# POWER.net
KiCad netlist of a schematic drawn in Altium Designer
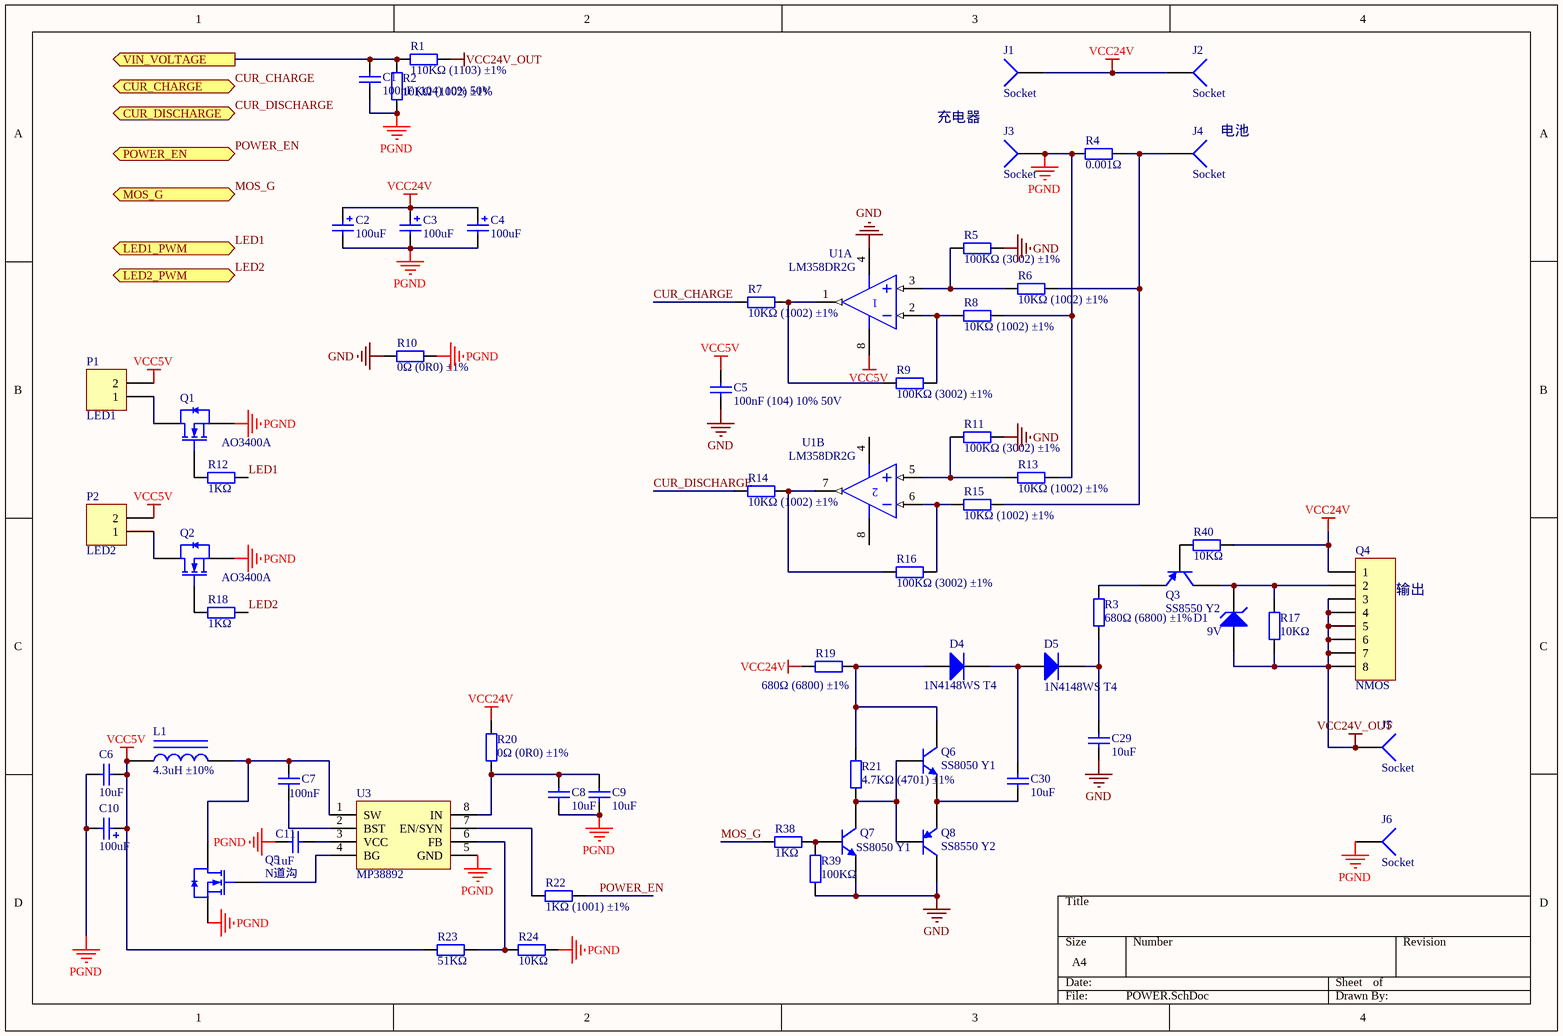
[diagram p0: POWER.SchDoc]

(export (version "E")
  (design (tool "Eeschema 10.0.6"))
  (components
    (comp (ref "C1")
      (value "100nF (104) 10% 50V")
      (footprint "0603_C")
      (description "贴片电容")
      (libsource (lib "Miscellaneous Devices LC") (part "0603 100nF (104) 10% 50V"))
    )
    (comp (ref "C2")
      (value "100uF")
      (footprint "CC6.56.5")
      (description "钽电容")
      (libsource (lib "Miscellaneous Devices LC") (part "3528 100uF (107) 10% 6.3V"))
    )
    (comp (ref "C3")
      (value "100uF")
      (footprint "CC6.56.5")
      (description "钽电容")
      (libsource (lib "Miscellaneous Devices LC") (part "3528 100uF (107) 10% 6.3V"))
    )
    (comp (ref "C4")
      (value "100uF")
      (footprint "CC6.56.5")
      (description "钽电容")
      (libsource (lib "Miscellaneous Devices LC") (part "3528 100uF (107) 10% 6.3V"))
    )
    (comp (ref "C5")
      (value "100nF (104) 10% 50V")
      (footprint "0603_C")
      (description "贴片电容")
      (libsource (lib "Miscellaneous Devices LC") (part "0603 100nF (104) 10% 50V"))
    )
    (comp (ref "C6")
      (value "10uF")
      (footprint "0805_C")
      (description "贴片电容")
      (libsource (lib "Miscellaneous Devices LC") (part "0805 10uF (106) 10% 25V"))
    )
    (comp (ref "C7")
      (value "100nF")
      (footprint "0603_C")
      (description "贴片电容")
      (libsource (lib "Miscellaneous Devices LC") (part "0603 100nF (104) 10% 50V"))
    )
    (comp (ref "C8")
      (value "10uF")
      (footprint "0805_C")
      (description "贴片电容")
      (libsource (lib "Miscellaneous Devices LC") (part "0805 10uF (106) 10% 25V"))
    )
    (comp (ref "C9")
      (value "10uF")
      (footprint "0805_C")
      (description "贴片电容")
      (libsource (lib "Miscellaneous Devices LC") (part "0805 10uF (106) 10% 25V"))
    )
    (comp (ref "C10")
      (value "100uF")
      (footprint "CC6.56.5")
      (description "钽电容")
      (libsource (lib "Miscellaneous Devices LC") (part "3528 100uF (107) 10% 6.3V"))
    )
    (comp (ref "C11")
      (value "1uF")
      (footprint "0603_C")
      (description "贴片电容")
      (libsource (lib "Miscellaneous Devices LC") (part "0603 1uF (105) 10% 50V"))
    )
    (comp (ref "C29")
      (value "10uF")
      (footprint "0805_C")
      (description "贴片电容")
      (libsource (lib "Miscellaneous Devices LC") (part "0805 10uF (106) 10% 25V"))
    )
    (comp (ref "C30")
      (value "10uF")
      (footprint "0805_C")
      (description "贴片电容")
      (libsource (lib "Miscellaneous Devices LC") (part "0805 10uF (106) 10% 25V"))
    )
    (comp (ref "D1")
      (value "9V")
      (footprint "LL-34")
      (description "稳压二极管")
      (libsource (lib "Miscellaneous Devices LC") (part "LL-34 ZMM5V6"))
    )
    (comp (ref "D4")
      (value "1N4148WS T4")
      (footprint "SOD-323")
      (description "二极管")
      (libsource (lib "Miscellaneous Devices LC") (part "SOD-323 1N4148WS T4"))
    )
    (comp (ref "D5")
      (value "1N4148WS T4")
      (footprint "SOD-323")
      (description "二极管")
      (libsource (lib "Miscellaneous Devices LC") (part "SOD-323 1N4148WS T4"))
    )
    (comp (ref "J1")
      (value "Socket")
      (footprint "PIN1")
      (fields (field (name "PUBLISHER") "Altium Limited"))
      (libsource (lib "Miscellaneous Connectors") (part "Socket"))
    )
    (comp (ref "J2")
      (value "Socket")
      (footprint "PIN1")
      (fields (field (name "PUBLISHER") "Altium Limited"))
      (libsource (lib "Miscellaneous Connectors") (part "Socket"))
    )
    (comp (ref "J3")
      (value "Socket")
      (footprint "PIN1")
      (fields (field (name "PUBLISHER") "Altium Limited"))
      (libsource (lib "Miscellaneous Connectors") (part "Socket"))
    )
    (comp (ref "J4")
      (value "Socket")
      (footprint "PIN1")
      (fields (field (name "PUBLISHER") "Altium Limited"))
      (libsource (lib "Miscellaneous Connectors") (part "Socket"))
    )
    (comp (ref "J5")
      (value "Socket")
      (footprint "PIN1")
      (fields (field (name "PUBLISHER") "Altium Limited"))
      (libsource (lib "Miscellaneous Connectors") (part "Socket"))
    )
    (comp (ref "J6")
      (value "Socket")
      (footprint "PIN1")
      (fields (field (name "PUBLISHER") "Altium Limited"))
      (libsource (lib "Miscellaneous Connectors") (part "Socket"))
    )
    (comp (ref "L1")
      (value "4.3uH ±10%")
      (footprint "2225")
      (description "贴片电感")
      (libsource (lib "Miscellaneous Devices LC") (part "0805 10uH 10%"))
    )
    (comp (ref "P1")
      (value "LED1")
      (footprint "HDR1X2")
      (description "Header, 2-Pin")
      (fields (field (name "PUBLISHER") "Altium Limited"))
      (libsource (lib "Miscellaneous Connectors") (part "Header 2"))
    )
    (comp (ref "P2")
      (value "LED2")
      (footprint "HDR1X2")
      (description "Header, 2-Pin")
      (fields (field (name "PUBLISHER") "Altium Limited"))
      (libsource (lib "Miscellaneous Connectors") (part "Header 2"))
    )
    (comp (ref "Q1")
      (value "AO3400A")
      (footprint "SOT-23-3L")
      (description "MOS(场效应管)")
      (libsource (lib "Miscellaneous Devices LC") (part "AO3400A N道沟 X0YV1T SOT-23"))
    )
    (comp (ref "Q2")
      (value "AO3400A")
      (footprint "SOT-23-3L")
      (description "MOS(场效应管)")
      (libsource (lib "Miscellaneous Devices LC") (part "AO3400A N道沟 X0YV1T SOT-23"))
    )
    (comp (ref "Q3")
      (value "SS8550 Y2")
      (footprint "SOT-23(SOT-23-3)")
      (description "三极管")
      (libsource (lib "Miscellaneous Devices LC") (part "SOT-23 SS8550 Y2"))
    )
    (comp (ref "Q4")
      (value "NMOS")
      (footprint "TO-263-7")
      (description "Header, 8-Pin")
      (fields (field (name "PUBLISHER") "Altium Limited"))
      (libsource (lib "Miscellaneous Connectors") (part "Header 8"))
    )
    (comp (ref "Q5")
      (value "N道沟")
      (footprint "TO-252-2")
      (description "MOS(场效应管)")
      (libsource (lib "Miscellaneous Devices LC") (part "AO3400A N道沟 X0YV1T SOT-23"))
    )
    (comp (ref "Q6")
      (value "SS8050 Y1")
      (footprint "SOT-23(SOT-23-3)")
      (description "三极管")
      (libsource (lib "Miscellaneous Devices LC") (part "SOT-23 SS8050 Y1"))
    )
    (comp (ref "Q7")
      (value "SS8050 Y1")
      (footprint "SOT-23(SOT-23-3)")
      (description "三极管")
      (libsource (lib "Miscellaneous Devices LC") (part "SOT-23 SS8050 Y1"))
    )
    (comp (ref "Q8")
      (value "SS8550 Y2")
      (footprint "SOT-23(SOT-23-3)")
      (description "三极管")
      (libsource (lib "Miscellaneous Devices LC") (part "SOT-23 SS8550 Y2"))
    )
    (comp (ref "R1")
      (value "110KΩ (1103) ±1%")
      (footprint "0603_R")
      (description "贴片电阻")
      (libsource (lib "Miscellaneous Devices LC") (part "0603 110KΩ (1103) 1%"))
    )
    (comp (ref "R2")
      (value "10KΩ (1002) ±1%")
      (footprint "0603_R")
      (description "贴片电阻")
      (libsource (lib "") (part "0603 10KΩ (1002) 1%_1"))
    )
    (comp (ref "R3")
      (value "680Ω (6800) ±1%")
      (footprint "0603_R")
      (description "贴片电阻")
      (libsource (lib "") (part "0603 680Ω (6800) 1%_1"))
    )
    (comp (ref "R4")
      (value "0.001Ω")
      (footprint "2512_R")
      (description "贴片电阻")
      (libsource (lib "") (part "0603 0Ω (0R0) 1%_1"))
    )
    (comp (ref "R5")
      (value "100KΩ (3002) ±1%")
      (footprint "0603_R")
      (description "贴片电阻")
      (libsource (lib "") (part "0603 30KΩ (3002) 1%_2"))
    )
    (comp (ref "R6")
      (value "10KΩ (1002) ±1%")
      (footprint "0603_R")
      (description "贴片电阻")
      (libsource (lib "Miscellaneous Devices LC") (part "0603 10KΩ (1002) 1%"))
    )
    (comp (ref "R7")
      (value "10KΩ (1002) ±1%")
      (footprint "0603_R")
      (description "贴片电阻")
      (libsource (lib "Miscellaneous Devices LC") (part "0603 10KΩ (1002) 1%"))
    )
    (comp (ref "R8")
      (value "10KΩ (1002) ±1%")
      (footprint "0603_R")
      (description "贴片电阻")
      (libsource (lib "Miscellaneous Devices LC") (part "0603 10KΩ (1002) 1%"))
    )
    (comp (ref "R9")
      (value "100KΩ (3002) ±1%")
      (footprint "0603_R")
      (description "贴片电阻")
      (libsource (lib "Miscellaneous Devices LC") (part "0603 30KΩ (3002) 1%"))
    )
    (comp (ref "R10")
      (value "0Ω (0R0) ±1%")
      (footprint "0603_R")
      (description "贴片电阻")
      (libsource (lib "") (part "0603 0Ω (0R0) 1%_2"))
    )
    (comp (ref "R11")
      (value "100KΩ (3002) ±1%")
      (footprint "0603_R")
      (description "贴片电阻")
      (libsource (lib "") (part "0603 30KΩ (3002) 1%_2"))
    )
    (comp (ref "R12")
      (value "1KΩ")
      (footprint "0603_R")
      (description "贴片电阻")
      (libsource (lib "Miscellaneous Devices LC") (part "0603 1KΩ (1001) 1%"))
    )
    (comp (ref "R13")
      (value "10KΩ (1002) ±1%")
      (footprint "0603_R")
      (description "贴片电阻")
      (libsource (lib "Miscellaneous Devices LC") (part "0603 10KΩ (1002) 1%"))
    )
    (comp (ref "R14")
      (value "10KΩ (1002) ±1%")
      (footprint "0603_R")
      (description "贴片电阻")
      (libsource (lib "Miscellaneous Devices LC") (part "0603 10KΩ (1002) 1%"))
    )
    (comp (ref "R15")
      (value "10KΩ (1002) ±1%")
      (footprint "0603_R")
      (description "贴片电阻")
      (libsource (lib "Miscellaneous Devices LC") (part "0603 10KΩ (1002) 1%"))
    )
    (comp (ref "R16")
      (value "100KΩ (3002) ±1%")
      (footprint "0603_R")
      (description "贴片电阻")
      (libsource (lib "Miscellaneous Devices LC") (part "0603 30KΩ (3002) 1%"))
    )
    (comp (ref "R17")
      (value "10KΩ")
      (footprint "0603_R")
      (description "贴片电阻")
      (libsource (lib "") (part "0603 10KΩ (1002) 1%_1"))
    )
    (comp (ref "R18")
      (value "1KΩ")
      (footprint "0603_R")
      (description "贴片电阻")
      (libsource (lib "Miscellaneous Devices LC") (part "0603 1KΩ (1001) 1%"))
    )
    (comp (ref "R19")
      (value "680Ω (6800) ±1%")
      (footprint "0603_R")
      (description "贴片电阻")
      (libsource (lib "Miscellaneous Devices LC") (part "0603 680Ω (6800) 1%"))
    )
    (comp (ref "R20")
      (value "0Ω (0R0) ±1%")
      (footprint "0603_R")
      (description "贴片电阻")
      (libsource (lib "Miscellaneous Devices LC") (part "0603 0Ω (0R0) 1%"))
    )
    (comp (ref "R21")
      (value "4.7KΩ (4701) ±1%")
      (footprint "0603_R")
      (description "贴片电阻")
      (libsource (lib "Miscellaneous Devices LC") (part "0603 4.7KΩ (4701) 1%"))
    )
    (comp (ref "R22")
      (value "1KΩ (1001) ±1%")
      (footprint "0603_R")
      (description "贴片电阻")
      (libsource (lib "") (part "0603 1KΩ (1001) 1%_1"))
    )
    (comp (ref "R23")
      (value "51KΩ")
      (footprint "0603_R")
      (description "贴片电阻")
      (libsource (lib "Miscellaneous Devices LC") (part "0603 51KΩ (5102) 1%"))
    )
    (comp (ref "R24")
      (value "10KΩ")
      (footprint "0603_R")
      (description "贴片电阻")
      (libsource (lib "") (part "0603 10KΩ (1002) 1%_2"))
    )
    (comp (ref "R38")
      (value "1KΩ")
      (footprint "0603_R")
      (description "贴片电阻")
      (libsource (lib "") (part "0603 1KΩ (1001) 1%_1"))
    )
    (comp (ref "R39")
      (value "100KΩ")
      (footprint "0603_R")
      (description "贴片电阻")
      (libsource (lib "") (part "0603 30KΩ (3002) 1%_1"))
    )
    (comp (ref "R40")
      (value "10KΩ")
      (footprint "0603_R")
      (description "贴片电阻")
      (libsource (lib "") (part "0603 10KΩ (1002) 1%_2"))
    )
    (comp (ref "U1")
      (value "LM358DR2G")
      (footprint "SOIC-8_150mil")
      (description "通用运放")
      (libsource (lib "Miscellaneous Devices LC") (part "LM358DR2G"))
    )
    (comp (ref "U3")
      (value "MP38892")
      (footprint "SOIC-8_EP_150mil")
      (libsource (lib "MySchlib") (part "MP38892"))
    )
  )
  (nets
    (net (code "1") (name "/CUR_CHARGE") (class "Default")
      (node (ref "R7") (pin "1") (pinfunction "1_1") (pintype "passive"))
    )
    (net (code "2") (name "/CUR_DISCHARGE") (class "Default")
      (node (ref "R14") (pin "1") (pinfunction "1_1") (pintype "passive"))
    )
    (net (code "3") (name "/LED1") (class "Default")
      (node (ref "R12") (pin "1") (pinfunction "1_1") (pintype "passive"))
    )
    (net (code "4") (name "/LED2") (class "Default")
      (node (ref "R18") (pin "1") (pinfunction "1_1") (pintype "passive"))
    )
    (net (code "5") (name "/MOS_G") (class "Default")
      (node (ref "R38") (pin "1") (pinfunction "1_1") (pintype "passive"))
    )
    (net (code "6") (name "/POWER_EN") (class "Default")
      (node (ref "R22") (pin "2") (pinfunction "2_2") (pintype "passive"))
    )
    (net (code "7") (name "/VIN_VOLTAGE") (class "Default")
      (node (ref "C1") (pin "1") (pinfunction "1_1") (pintype "passive"))
      (node (ref "R1") (pin "2") (pinfunction "2_2") (pintype "passive"))
      (node (ref "R2") (pin "2") (pinfunction "2_2") (pintype "passive"))
    )
    (net (code "8") (name "GND") (class "Default")
      (node (ref "C29") (pin "1") (pinfunction "1_1") (pintype "passive"))
      (node (ref "C5") (pin "2") (pinfunction "2_2") (pintype "passive"))
      (node (ref "Q7") (pin "2") (pinfunction "E_2") (pintype "passive"))
      (node (ref "Q8") (pin "3") (pinfunction "C_3") (pintype "passive"))
      (node (ref "R10") (pin "1") (pinfunction "1_1") (pintype "passive"))
      (node (ref "R11") (pin "1") (pinfunction "1_1") (pintype "passive"))
      (node (ref "R39") (pin "1") (pinfunction "1_1") (pintype "passive"))
      (node (ref "R5") (pin "1") (pinfunction "1_1") (pintype "passive"))
      (node (ref "U1") (pin "4") (pinfunction "V-_4") (pintype "power_in"))
    )
    (net (code "9") (name "Net-(D1-K)") (class "Default")
      (node (ref "D1") (pin "2") (pinfunction "K_2") (pintype "passive"))
      (node (ref "Q3") (pin "3") (pinfunction "C_3") (pintype "passive"))
      (node (ref "Q4") (pin "2") (pinfunction "2_2") (pintype "passive"))
      (node (ref "R17") (pin "2") (pinfunction "2_2") (pintype "passive"))
    )
    (net (code "10") (name "Net-(D4-A)") (class "Default")
      (node (ref "D4") (pin "1") (pinfunction "A_1") (pintype "passive"))
      (node (ref "Q6") (pin "3") (pinfunction "C_3") (pintype "passive"))
      (node (ref "R19") (pin "1") (pinfunction "1_1") (pintype "passive"))
      (node (ref "R21") (pin "2") (pinfunction "2_2") (pintype "passive"))
    )
    (net (code "11") (name "Net-(D4-K)") (class "Default")
      (node (ref "C30") (pin "2") (pinfunction "2_2") (pintype "passive"))
      (node (ref "D4") (pin "2") (pinfunction "K_2") (pintype "passive"))
      (node (ref "D5") (pin "1") (pinfunction "A_1") (pintype "passive"))
    )
    (net (code "12") (name "Net-(D5-K)") (class "Default")
      (node (ref "C29") (pin "2") (pinfunction "2_2") (pintype "passive"))
      (node (ref "D5") (pin "2") (pinfunction "K_2") (pintype "passive"))
      (node (ref "R3") (pin "2") (pinfunction "2_2") (pintype "passive"))
    )
    (net (code "13") (name "Net-(J4-Pad1)") (class "Default")
      (node (ref "J4") (pin "1") (pinfunction "1_1") (pintype "passive"))
      (node (ref "R15") (pin "2") (pinfunction "2_2") (pintype "passive"))
      (node (ref "R4") (pin "1") (pinfunction "1_1") (pintype "passive"))
      (node (ref "R6") (pin "2") (pinfunction "2_2") (pintype "passive"))
    )
    (net (code "14") (name "Net-(Q1-D)") (class "Default")
      (node (ref "P1") (pin "1") (pinfunction "1_1") (pintype "passive"))
      (node (ref "Q1") (pin "3") (pinfunction "D_3") (pintype "passive"))
    )
    (net (code "15") (name "Net-(Q1-G)") (class "Default")
      (node (ref "Q1") (pin "1") (pinfunction "G_1") (pintype "passive"))
      (node (ref "R12") (pin "2") (pinfunction "2_2") (pintype "passive"))
    )
    (net (code "16") (name "Net-(Q2-D)") (class "Default")
      (node (ref "P2") (pin "1") (pinfunction "1_1") (pintype "passive"))
      (node (ref "Q2") (pin "3") (pinfunction "D_3") (pintype "passive"))
    )
    (net (code "17") (name "Net-(Q2-G)") (class "Default")
      (node (ref "Q2") (pin "1") (pinfunction "G_1") (pintype "passive"))
      (node (ref "R18") (pin "2") (pinfunction "2_2") (pintype "passive"))
    )
    (net (code "18") (name "Net-(Q3-B)") (class "Default")
      (node (ref "Q3") (pin "1") (pinfunction "B_1") (pintype "passive"))
      (node (ref "R40") (pin "2") (pinfunction "2_2") (pintype "passive"))
    )
    (net (code "19") (name "Net-(Q3-E)") (class "Default")
      (node (ref "Q3") (pin "2") (pinfunction "E_2") (pintype "passive"))
      (node (ref "R3") (pin "1") (pinfunction "1_1") (pintype "passive"))
    )
    (net (code "20") (name "Net-(Q5-D)") (class "Default")
      (node (ref "C7") (pin "2") (pinfunction "2_2") (pintype "passive"))
      (node (ref "L1") (pin "2") (pinfunction "2_2") (pintype "passive"))
      (node (ref "Q5") (pin "3") (pinfunction "D_3") (pintype "passive"))
      (node (ref "U3") (pin "1") (pinfunction "SW_1") (pintype "passive"))
    )
    (net (code "21") (name "Net-(Q5-G)") (class "Default")
      (node (ref "Q5") (pin "1") (pinfunction "G_1") (pintype "passive"))
      (node (ref "U3") (pin "4") (pinfunction "BG_4") (pintype "passive"))
    )
    (net (code "22") (name "Net-(Q6-B)") (class "Default")
      (node (ref "Q6") (pin "1") (pinfunction "B_1") (pintype "passive"))
      (node (ref "Q7") (pin "3") (pinfunction "C_3") (pintype "passive"))
      (node (ref "Q8") (pin "1") (pinfunction "B_1") (pintype "passive"))
      (node (ref "R21") (pin "1") (pinfunction "1_1") (pintype "passive"))
    )
    (net (code "23") (name "Net-(Q6-E)") (class "Default")
      (node (ref "C30") (pin "1") (pinfunction "1_1") (pintype "passive"))
      (node (ref "Q6") (pin "2") (pinfunction "E_2") (pintype "passive"))
      (node (ref "Q8") (pin "2") (pinfunction "E_2") (pintype "passive"))
    )
    (net (code "24") (name "Net-(Q7-B)") (class "Default")
      (node (ref "Q7") (pin "1") (pinfunction "B_1") (pintype "passive"))
      (node (ref "R38") (pin "2") (pinfunction "2_2") (pintype "passive"))
      (node (ref "R39") (pin "2") (pinfunction "2_2") (pintype "passive"))
    )
    (net (code "25") (name "Net-(U1A-IN+)") (class "Default")
      (node (ref "R5") (pin "2") (pinfunction "2_2") (pintype "passive"))
      (node (ref "R6") (pin "1") (pinfunction "1_1") (pintype "passive"))
      (node (ref "U1") (pin "3") (pinfunction "IN+_3") (pintype "input"))
    )
    (net (code "26") (name "Net-(U1A-IN-)") (class "Default")
      (node (ref "R8") (pin "1") (pinfunction "1_1") (pintype "passive"))
      (node (ref "R9") (pin "2") (pinfunction "2_2") (pintype "passive"))
      (node (ref "U1") (pin "2") (pinfunction "IN-_2") (pintype "input"))
    )
    (net (code "27") (name "Net-(U1A-OUT)") (class "Default")
      (node (ref "R7") (pin "2") (pinfunction "2_2") (pintype "passive"))
      (node (ref "R9") (pin "1") (pinfunction "1_1") (pintype "passive"))
      (node (ref "U1") (pin "1") (pinfunction "OUT_1") (pintype "output"))
    )
    (net (code "28") (name "Net-(U1B-IN+)") (class "Default")
      (node (ref "R11") (pin "2") (pinfunction "2_2") (pintype "passive"))
      (node (ref "R13") (pin "1") (pinfunction "1_1") (pintype "passive"))
      (node (ref "U1") (pin "5") (pinfunction "IN+_5") (pintype "input"))
    )
    (net (code "29") (name "Net-(U1B-IN-)") (class "Default")
      (node (ref "R15") (pin "1") (pinfunction "1_1") (pintype "passive"))
      (node (ref "R16") (pin "2") (pinfunction "2_2") (pintype "passive"))
      (node (ref "U1") (pin "6") (pinfunction "IN-_6") (pintype "input"))
    )
    (net (code "30") (name "Net-(U1B-OUT)") (class "Default")
      (node (ref "R14") (pin "2") (pinfunction "2_2") (pintype "passive"))
      (node (ref "R16") (pin "1") (pinfunction "1_1") (pintype "passive"))
      (node (ref "U1") (pin "7") (pinfunction "OUT_7") (pintype "output"))
    )
    (net (code "31") (name "Net-(U3-BST)") (class "Default")
      (node (ref "C7") (pin "1") (pinfunction "1_1") (pintype "passive"))
      (node (ref "U3") (pin "2") (pinfunction "BST_2") (pintype "passive"))
    )
    (net (code "32") (name "Net-(U3-EN{slash}SYN)") (class "Default")
      (node (ref "R22") (pin "1") (pinfunction "1_1") (pintype "passive"))
      (node (ref "U3") (pin "7") (pinfunction "EN/SYN_7") (pintype "passive"))
    )
    (net (code "33") (name "Net-(U3-FB)") (class "Default")
      (node (ref "R23") (pin "1") (pinfunction "1_1") (pintype "passive"))
      (node (ref "R24") (pin "2") (pinfunction "2_2") (pintype "passive"))
      (node (ref "U3") (pin "6") (pinfunction "FB_6") (pintype "passive"))
    )
    (net (code "34") (name "Net-(U3-IN)") (class "Default")
      (node (ref "C8") (pin "1") (pinfunction "1_1") (pintype "passive"))
      (node (ref "C9") (pin "1") (pinfunction "1_1") (pintype "passive"))
      (node (ref "R20") (pin "1") (pinfunction "1_1") (pintype "passive"))
      (node (ref "U3") (pin "8") (pinfunction "IN_8") (pintype "passive"))
    )
    (net (code "35") (name "Net-(U3-VCC)") (class "Default")
      (node (ref "C11") (pin "1") (pinfunction "1_1") (pintype "passive"))
      (node (ref "U3") (pin "3") (pinfunction "VCC_3") (pintype "passive"))
    )
    (net (code "36") (name "PGND") (class "Default")
      (node (ref "C1") (pin "2") (pinfunction "2_2") (pintype "passive"))
      (node (ref "C10") (pin "2") (pinfunction "2_2") (pintype "passive"))
      (node (ref "C11") (pin "2") (pinfunction "2_2") (pintype "passive"))
      (node (ref "C2") (pin "2") (pinfunction "2_2") (pintype "passive"))
      (node (ref "C3") (pin "2") (pinfunction "2_2") (pintype "passive"))
      (node (ref "C4") (pin "2") (pinfunction "2_2") (pintype "passive"))
      (node (ref "C6") (pin "2") (pinfunction "2_2") (pintype "passive"))
      (node (ref "C8") (pin "2") (pinfunction "2_2") (pintype "passive"))
      (node (ref "C9") (pin "2") (pinfunction "2_2") (pintype "passive"))
      (node (ref "J3") (pin "1") (pinfunction "1_1") (pintype "passive"))
      (node (ref "J6") (pin "1") (pinfunction "1_1") (pintype "passive"))
      (node (ref "Q1") (pin "2") (pinfunction "S_2") (pintype "passive"))
      (node (ref "Q2") (pin "2") (pinfunction "S_2") (pintype "passive"))
      (node (ref "Q5") (pin "2") (pinfunction "S_2") (pintype "passive"))
      (node (ref "R10") (pin "2") (pinfunction "2_2") (pintype "passive"))
      (node (ref "R13") (pin "2") (pinfunction "2_2") (pintype "passive"))
      (node (ref "R2") (pin "1") (pinfunction "1_1") (pintype "passive"))
      (node (ref "R24") (pin "1") (pinfunction "1_1") (pintype "passive"))
      (node (ref "R4") (pin "2") (pinfunction "2_2") (pintype "passive"))
      (node (ref "R8") (pin "2") (pinfunction "2_2") (pintype "passive"))
      (node (ref "U3") (pin "5") (pinfunction "GND_5") (pintype "passive"))
    )
    (net (code "37") (name "VCC5V") (class "Default")
      (node (ref "C10") (pin "1") (pinfunction "1_1") (pintype "passive"))
      (node (ref "C5") (pin "1") (pinfunction "1_1") (pintype "passive"))
      (node (ref "C6") (pin "1") (pinfunction "1_1") (pintype "passive"))
      (node (ref "L1") (pin "1") (pinfunction "1_1") (pintype "passive"))
      (node (ref "P1") (pin "2") (pinfunction "2_2") (pintype "passive"))
      (node (ref "P2") (pin "2") (pinfunction "2_2") (pintype "passive"))
      (node (ref "R23") (pin "2") (pinfunction "2_2") (pintype "passive"))
      (node (ref "U1") (pin "8") (pinfunction "V+_8") (pintype "power_in"))
    )
    (net (code "38") (name "VCC24V") (class "Default")
      (node (ref "C2") (pin "1") (pinfunction "1_1") (pintype "passive"))
      (node (ref "C3") (pin "1") (pinfunction "1_1") (pintype "passive"))
      (node (ref "C4") (pin "1") (pinfunction "1_1") (pintype "passive"))
      (node (ref "J1") (pin "1") (pinfunction "1_1") (pintype "passive"))
      (node (ref "J2") (pin "1") (pinfunction "1_1") (pintype "passive"))
      (node (ref "Q4") (pin "1") (pinfunction "1_1") (pintype "passive"))
      (node (ref "R19") (pin "2") (pinfunction "2_2") (pintype "passive"))
      (node (ref "R20") (pin "2") (pinfunction "2_2") (pintype "passive"))
      (node (ref "R40") (pin "1") (pinfunction "1_1") (pintype "passive"))
    )
    (net (code "39") (name "VCC24V_OUT") (class "Default")
      (node (ref "D1") (pin "1") (pinfunction "A_1") (pintype "passive"))
      (node (ref "J5") (pin "1") (pinfunction "1_1") (pintype "passive"))
      (node (ref "Q4") (pin "3") (pinfunction "3_3") (pintype "passive"))
      (node (ref "Q4") (pin "4") (pinfunction "4_4") (pintype "passive"))
      (node (ref "Q4") (pin "5") (pinfunction "5_5") (pintype "passive"))
      (node (ref "Q4") (pin "6") (pinfunction "6_6") (pintype "passive"))
      (node (ref "Q4") (pin "7") (pinfunction "7_7") (pintype "passive"))
      (node (ref "Q4") (pin "8") (pinfunction "8_8") (pintype "passive"))
      (node (ref "R1") (pin "1") (pinfunction "1_1") (pintype "passive"))
      (node (ref "R17") (pin "1") (pinfunction "1_1") (pintype "passive"))
    )
    (net (code "40") (name "unconnected-(U1B-V+-Pad8)") (class "Default")
      (node (ref "U1") (pin "8") (pinfunction "V+_8") (pintype "power_in"))
    )
    (net (code "41") (name "unconnected-(U1B-V--Pad4)") (class "Default")
      (node (ref "U1") (pin "4") (pinfunction "V-_4") (pintype "power_in"))
    )
  )
)
